# 4_TTL.net
KiCad netlist of a schematic drawn in EAGLE
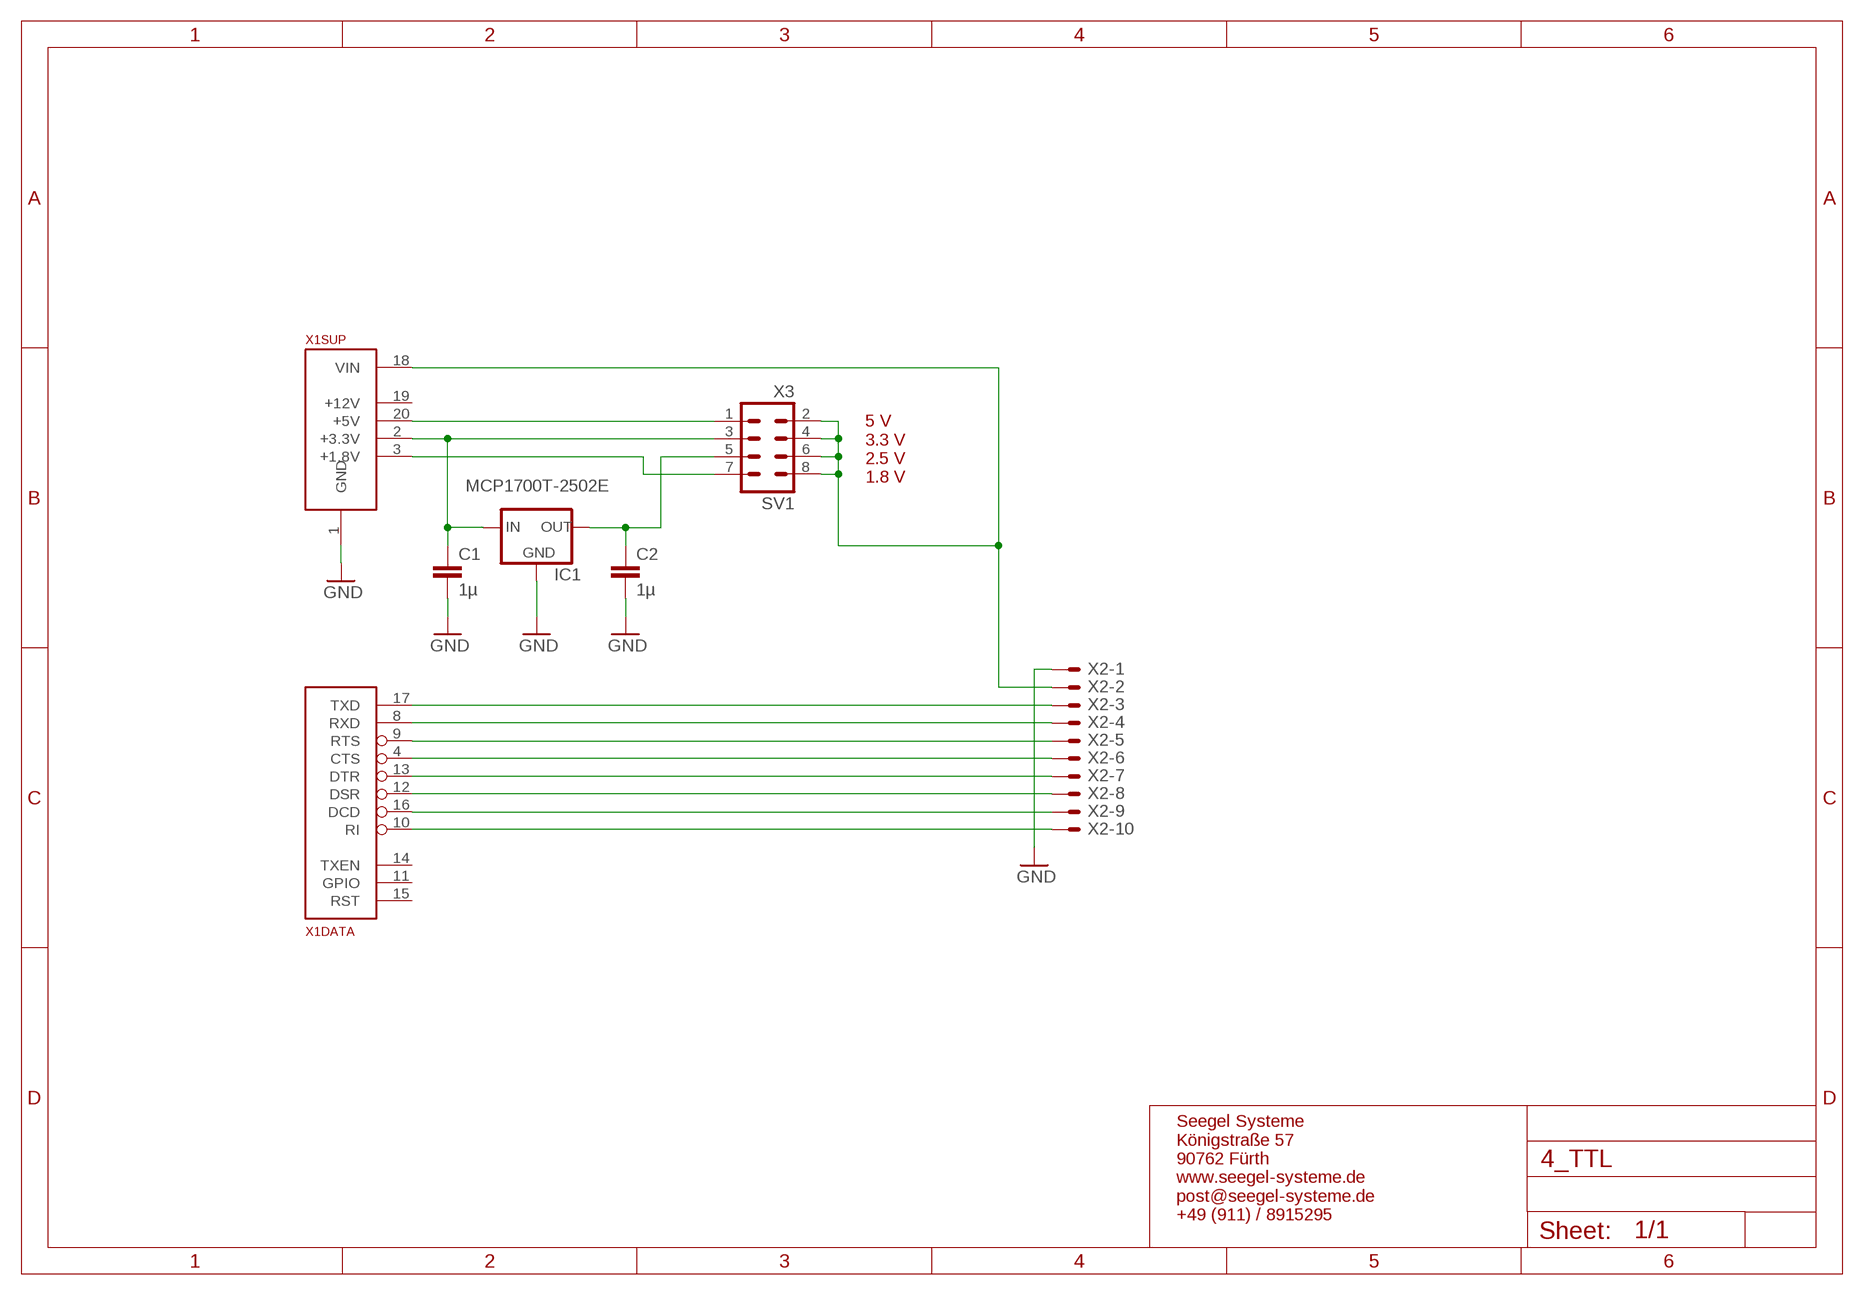
[diagram p0: schematic, sheet 1]

(export (version "E")
  (design (tool "Eeschema 10.0.6"))
  (components
    (comp (ref "C1")
      (value "1µ")
      (footprint "eagle-import:C0805K")
      (libsource (lib "eagle-import") (part "C-EUC0805K"))
    )
    (comp (ref "C2")
      (value "1µ")
      (footprint "eagle-import:C0805K")
      (libsource (lib "eagle-import") (part "C-EUC0805K"))
    )
    (comp (ref "IC1")
      (value "MCP1700T-2502E")
      (footprint "eagle-import:SOT23")
      (libsource (lib "eagle-import") (part "MCP170X"))
    )
    (comp (ref "SV1")
      (value "X3")
      (footprint "eagle-import:MA04-2W")
      (libsource (lib "eagle-import") (part "MA04-2W"))
    )
    (comp (ref "X1")
      (value "ALLSERIALSLAVE")
      (footprint "eagle-import:DAUGHTER-THT")
      (libsource (lib "eagle-import") (part "ALLSERIALSLAVE"))
    )
    (comp (ref "X2")
      (value "AKL18X-10W")
      (footprint "eagle-import:AKL182-10")
      (fields (field (name "OC_REICHELT") "AKL 182-10"))
      (libsource (lib "eagle-import") (part "AKL18X-10W"))
    )
  )
  (nets
    (net (code "1") (name "GND") (class "Default")
      (node (ref "C1") (pin "2") (pinfunction "2_2") (pintype "passive"))
      (node (ref "C2") (pin "2") (pinfunction "2_2") (pintype "passive"))
      (node (ref "IC1") (pin "1") (pinfunction "GND_1") (pintype "input"))
      (node (ref "X1") (pin "1") (pinfunction "GND_1") (pintype "bidirectional"))
      (node (ref "X2") (pin "P$1") (pinfunction "S_P$1") (pintype "passive"))
    )
    (net (code "2") (name "Net-(IC1-IN)") (class "Default")
      (node (ref "C1") (pin "1") (pinfunction "1_1") (pintype "passive"))
      (node (ref "IC1") (pin "3") (pinfunction "IN_3") (pintype "input"))
      (node (ref "SV1") (pin "3") (pinfunction "3_3") (pintype "passive"))
      (node (ref "X1") (pin "2") (pinfunction "+3.3V_2") (pintype "bidirectional"))
    )
    (net (code "3") (name "Net-(IC1-OUT)") (class "Default")
      (node (ref "C2") (pin "1") (pinfunction "1_1") (pintype "passive"))
      (node (ref "IC1") (pin "2") (pinfunction "OUT_2") (pintype "passive"))
      (node (ref "SV1") (pin "5") (pinfunction "5_5") (pintype "passive"))
    )
    (net (code "4") (name "Net-(X1A-CTS)") (class "Default")
      (node (ref "X1") (pin "4") (pinfunction "CTS_4") (pintype "input"))
      (node (ref "X2") (pin "P$6") (pinfunction "S_P$6") (pintype "passive"))
    )
    (net (code "5") (name "Net-(X1A-DCD)") (class "Default")
      (node (ref "X1") (pin "16") (pinfunction "DCD_16") (pintype "input"))
      (node (ref "X2") (pin "P$9") (pinfunction "S_P$9") (pintype "passive"))
    )
    (net (code "6") (name "Net-(X1A-DSR)") (class "Default")
      (node (ref "X1") (pin "12") (pinfunction "DSR_12") (pintype "input"))
      (node (ref "X2") (pin "P$8") (pinfunction "S_P$8") (pintype "passive"))
    )
    (net (code "7") (name "Net-(X1A-DTR)") (class "Default")
      (node (ref "X1") (pin "13") (pinfunction "DTR_13") (pintype "output"))
      (node (ref "X2") (pin "P$7") (pinfunction "S_P$7") (pintype "passive"))
    )
    (net (code "8") (name "Net-(X1A-RI)") (class "Default")
      (node (ref "X1") (pin "10") (pinfunction "RI_10") (pintype "input"))
      (node (ref "X2") (pin "P$10") (pinfunction "S_P$10") (pintype "passive"))
    )
    (net (code "9") (name "Net-(X1A-RTS)") (class "Default")
      (node (ref "X1") (pin "9") (pinfunction "RTS_9") (pintype "output"))
      (node (ref "X2") (pin "P$5") (pinfunction "S_P$5") (pintype "passive"))
    )
    (net (code "10") (name "Net-(X1A-RXD)") (class "Default")
      (node (ref "X1") (pin "8") (pinfunction "RXD_8") (pintype "input"))
      (node (ref "X2") (pin "P$4") (pinfunction "S_P$4") (pintype "passive"))
    )
    (net (code "11") (name "Net-(X1A-TXD)") (class "Default")
      (node (ref "X1") (pin "17") (pinfunction "TXD_17") (pintype "output"))
      (node (ref "X2") (pin "P$3") (pinfunction "S_P$3") (pintype "passive"))
    )
    (net (code "12") (name "Net-(X1B-+1.8V)") (class "Default")
      (node (ref "SV1") (pin "7") (pinfunction "7_7") (pintype "passive"))
      (node (ref "X1") (pin "3") (pinfunction "+1.8V_3") (pintype "bidirectional"))
    )
    (net (code "13") (name "Net-(X1B-+5V)") (class "Default")
      (node (ref "SV1") (pin "1") (pinfunction "1_1") (pintype "passive"))
      (node (ref "X1") (pin "20") (pinfunction "+5V_20") (pintype "bidirectional"))
    )
    (net (code "14") (name "Net-(X1B-VIN)") (class "Default")
      (node (ref "SV1") (pin "2") (pinfunction "2_2") (pintype "passive"))
      (node (ref "SV1") (pin "4") (pinfunction "4_4") (pintype "passive"))
      (node (ref "SV1") (pin "6") (pinfunction "6_6") (pintype "passive"))
      (node (ref "SV1") (pin "8") (pinfunction "8_8") (pintype "passive"))
      (node (ref "X1") (pin "18") (pinfunction "VIN_18") (pintype "bidirectional"))
      (node (ref "X2") (pin "P$2") (pinfunction "S_P$2") (pintype "passive"))
    )
    (net (code "15") (name "unconnected-(X1A-GPIO-Pad11)") (class "Default")
      (node (ref "X1") (pin "11") (pinfunction "GPIO_11") (pintype "bidirectional"))
    )
    (net (code "16") (name "unconnected-(X1A-RST-Pad15)") (class "Default")
      (node (ref "X1") (pin "15") (pinfunction "RST_15") (pintype "bidirectional"))
    )
    (net (code "17") (name "unconnected-(X1A-TXEN-Pad14)") (class "Default")
      (node (ref "X1") (pin "14") (pinfunction "TXEN_14") (pintype "output"))
    )
    (net (code "18") (name "unconnected-(X1B-+12V-Pad19)") (class "Default")
      (node (ref "X1") (pin "19") (pinfunction "+12V_19") (pintype "bidirectional"))
    )
  )
)
